# P03_Processor_1_of_3_JTAG_Header.net
KiCad netlist of a schematic drawn in Altium Designer
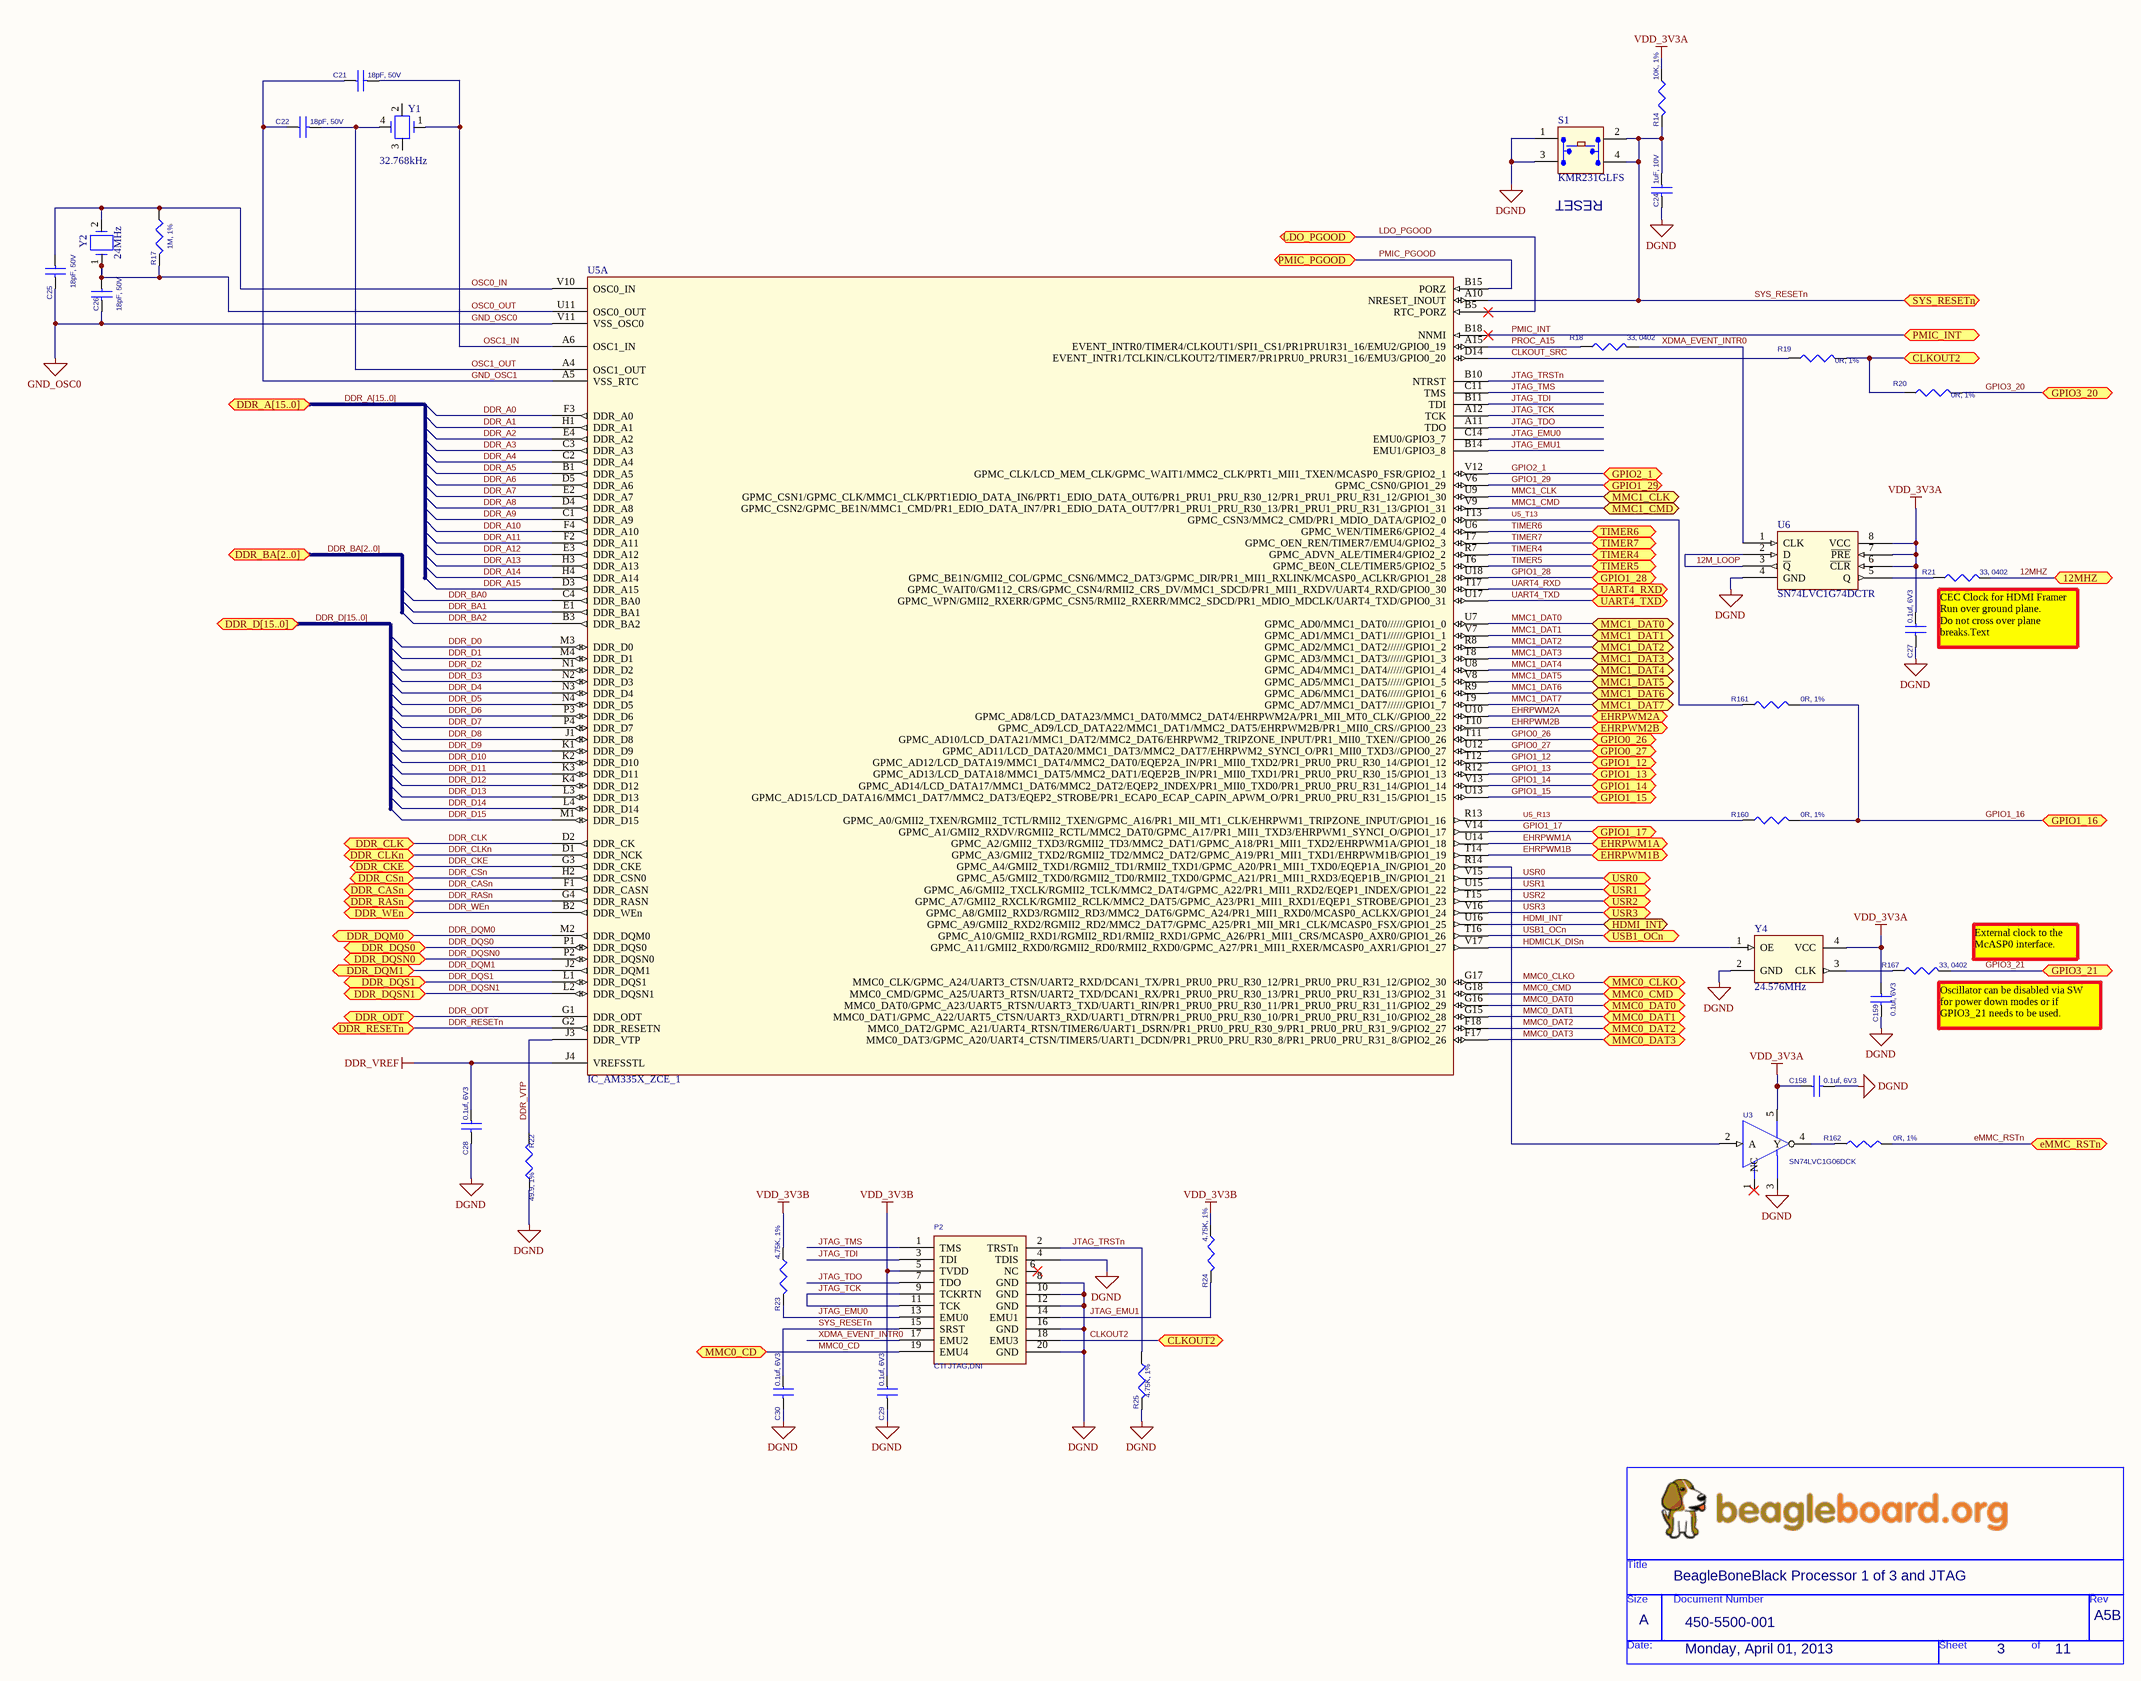
[diagram p0: P03_Processor 1 of 3, JTAG Header.SchDoc]

(export (version "E")
  (design (tool "Eeschema 10.0.6"))
  (components
    (comp (ref "C21")
      (value "18pF, 50V")
      (footprint "402")
      (description "CAP CER 18PF 50V 5% NP0 0402")
      (fields
        (field (name "MANUFACTURER") "TDK Corporation")
        (field (name "MANUFACTURER PART NUMBER") "C1005C0G1H180J050BA")
      )
      (libsource (lib "BEAGLEBONEBLACK_REV A5B") (part "CAP_18PF_COG_50V_5%_0402"))
    )
    (comp (ref "C22")
      (value "18pF, 50V")
      (footprint "402")
      (description "CAP CER 18PF 50V 5% NP0 0402")
      (fields
        (field (name "MANUFACTURER") "TDK Corporation")
        (field (name "MANUFACTURER PART NUMBER") "C1005C0G1H180J050BA")
      )
      (libsource (lib "BEAGLEBONEBLACK_REV A5B") (part "CAP_18PF_COG_50V_5%_0402"))
    )
    (comp (ref "C24")
      (value "1uF, 10V")
      (footprint "402")
      (description "CAP CER 1UF 10V 10% X5R 0402")
      (fields
        (field (name "MANUFACTURER") "AVX Corporation")
        (field (name "MANUFACTURER PART NUMBER") "0402ZD105KAT2A")
      )
      (libsource (lib "BEAGLEBONEBLACK_REV A5B") (part "CAP_1.0UF_X5R_10V_10%_0402"))
    )
    (comp (ref "C25")
      (value "18pF, 50V")
      (footprint "402")
      (description "CAP CER 18PF 50V 5% NP0 0402")
      (fields
        (field (name "MANUFACTURER") "TDK Corporation")
        (field (name "MANUFACTURER PART NUMBER") "C1005C0G1H180J050BA")
      )
      (libsource (lib "BEAGLEBONEBLACK_REV A5B") (part "CAP_18PF_COG_50V_5%_0402"))
    )
    (comp (ref "C26")
      (value "18pF, 50V")
      (footprint "402")
      (description "CAP CER 18PF 50V 5% NP0 0402")
      (fields
        (field (name "MANUFACTURER") "TDK Corporation")
        (field (name "MANUFACTURER PART NUMBER") "C1005C0G1H180J050BA")
      )
      (libsource (lib "BEAGLEBONEBLACK_REV A5B") (part "CAP_18PF_COG_50V_5%_0402"))
    )
    (comp (ref "C27")
      (value "0.1uf, 6V3")
      (footprint "402")
      (description "CAP CER 0.1UF 6.3V 10% X5R 0402")
      (fields
        (field (name "MANUFACTURER") "TDK Corporation")
        (field (name "MANUFACTURER PART NUMBER") "C1005X5R0J104K050BA")
      )
      (libsource (lib "BEAGLEBONEBLACK_REV A5B") (part "CAP_0.1uF_X7R_16V_10% 0402"))
    )
    (comp (ref "C28")
      (value "0.1uf, 6V3")
      (footprint "402")
      (description "CAP CER 0.1UF 6.3V 10% X5R 0402")
      (fields
        (field (name "MANUFACTURER") "TDK Corporation")
        (field (name "MANUFACTURER PART NUMBER") "C1005X5R0J104K050BA")
      )
      (libsource (lib "BEAGLEBONEBLACK_REV A5B") (part "CAP_0.1uF_X7R_16V_10% 0402"))
    )
    (comp (ref "C29")
      (value "0.1uf, 6V3")
      (footprint "402")
      (description "CAP CER 0.1UF 6.3V 10% X5R 0402")
      (fields
        (field (name "MANUFACTURER") "TDK Corporation")
        (field (name "MANUFACTURER PART NUMBER") "C1005X5R0J104K050BA")
      )
      (libsource (lib "BEAGLEBONEBLACK_REV A5B") (part "CAP_0.1uF_X7R_16V_10% 0402"))
    )
    (comp (ref "C30")
      (value "0.1uf, 6V3")
      (footprint "402")
      (description "CAP CER 0.1UF 6.3V 10% X5R 0402")
      (fields
        (field (name "MANUFACTURER") "TDK Corporation")
        (field (name "MANUFACTURER PART NUMBER") "C1005X5R0J104K050BA")
      )
      (libsource (lib "BEAGLEBONEBLACK_REV A5B") (part "CAP_0.1uF_X7R_16V_10% 0402"))
    )
    (comp (ref "C158")
      (value "0.1uf, 6V3")
      (footprint "402")
      (description "CAP CER 0.1UF 6.3V 10% X5R 0402")
      (fields
        (field (name "MANUFACTURER") "TDK Corporation")
        (field (name "MANUFACTURER PART NUMBER") "C1005X5R0J104K050BA")
      )
      (libsource (lib "BEAGLEBONEBLACK_REV A5B") (part "CAP_0.1uF_X7R_16V_10% 0402"))
    )
    (comp (ref "C159")
      (value "0.1uf, 6V3")
      (footprint "402")
      (description "CAP CER 0.1UF 6.3V 10% X5R 0402")
      (fields
        (field (name "MANUFACTURER") "TDK Corporation")
        (field (name "MANUFACTURER PART NUMBER") "C1005X5R0J104K050BA")
      )
      (libsource (lib "BEAGLEBONEBLACK_REV A5B") (part "CAP_0.1uF_X7R_16V_10% 0402"))
    )
    (comp (ref "P2")
      (value "CTI JTAG,DNI")
      (description "Dual Line Header 10x2pin Tin")
      (fields
        (field (name "MANUFACTURER") "Samtec Inc")
        (field (name "MANUFACTURER PART NUMBER") "FTR-110-03-G-D-06")
      )
      (libsource (lib "BEAGLEBONEBLACK_REV A5B") (part "HDR_10x2_CJTAG"))
    )
    (comp (ref "R14")
      (value "10K, 1%")
      (footprint "402")
      (description "RES 10K OHM 1/16W 5% 0402 SMD")
      (fields
        (field (name "MANUFACTURER") "Rohm Semiconductor")
        (field (name "MANUFACTURER PART NUMBER") "MCR01MZPJ103")
      )
      (libsource (lib "BEAGLEBONEBLACK_REV A5B") (part "RES_10K_1/16W_1%_0402"))
    )
    (comp (ref "R17")
      (value "1M, 1%")
      (footprint "402")
      (description "Resistor 1Mohm 1/16W 1% 0402")
      (fields
        (field (name "MANUFACTURER") "Stackpole Electronics Inc")
        (field (name "MANUFACTURER PART NUMBER") "RMCF0402FT1M00")
      )
      (libsource (lib "BEAGLEBONEBLACK_REV A5B") (part "RES_1M_1/16W_1%_0402"))
    )
    (comp (ref "R18")
      (value "33, 0402")
      (footprint "402")
      (description "RES 33 OHM 1/16W 5% 0402 SMD")
      (fields
        (field (name "MANUFACTURER") "Panasonic Electronic Components")
        (field (name "MANUFACTURER PART NUMBER") "ERJ-2GEJ330X")
      )
      (libsource (lib "BEAGLEBONEBLACK_REV A5B") (part "RES_33_0402"))
    )
    (comp (ref "R19")
      (value "0R, 1%")
      (footprint "402")
      (description "RES 0.0 OHM 1/16W 0402 SMD")
      (fields
        (field (name "MANUFACTURER") "Yageo")
        (field (name "MANUFACTURER PART NUMBER") "RC0402JR-070RL")
      )
      (libsource (lib "BEAGLEBONEBLACK_REV A5B") (part "RES_0_1/16W_1%_0402"))
    )
    (comp (ref "R20")
      (value "0R, 1%")
      (footprint "402")
      (description "RES 0.0 OHM 1/16W 0402 SMD")
      (fields
        (field (name "MANUFACTURER") "Yageo")
        (field (name "MANUFACTURER PART NUMBER") "RC0402JR-070RL")
      )
      (libsource (lib "BEAGLEBONEBLACK_REV A5B") (part "RES_0_1/16W_1%_0402"))
    )
    (comp (ref "R21")
      (value "33, 0402")
      (footprint "402")
      (description "RES 33 OHM 1/16W 5% 0402 SMD")
      (fields
        (field (name "MANUFACTURER") "Panasonic Electronic Components")
        (field (name "MANUFACTURER PART NUMBER") "ERJ-2GEJ330X")
      )
      (libsource (lib "BEAGLEBONEBLACK_REV A5B") (part "RES_33_0402"))
    )
    (comp (ref "R22")
      (value "49.9, 1%")
      (footprint "402")
      (description "RES 49.9 OHM 1/16W 1% 0402 SMD")
      (fields
        (field (name "MANUFACTURER") "Yageo")
        (field (name "MANUFACTURER PART NUMBER") "RC0402FR-0749R9L")
      )
      (libsource (lib "BEAGLEBONEBLACK_REV A5B") (part "RES_4.7K_0402"))
    )
    (comp (ref "R23")
      (value "4.75K, 1%")
      (footprint "402")
      (description "RES 4.75K 1/16W 1% 0402 SMD")
      (fields
        (field (name "MANUFACTURER") "Stackpole Electronics Inc")
        (field (name "MANUFACTURER PART NUMBER") "RMCF0402FT4K75")
      )
      (libsource (lib "BEAGLEBONEBLACK_REV A5B") (part "RES_4.7K_0402"))
    )
    (comp (ref "R24")
      (value "4.75K, 1%")
      (footprint "402")
      (description "RES 4.75K 1/16W 1% 0402 SMD")
      (fields
        (field (name "MANUFACTURER") "Stackpole Electronics Inc")
        (field (name "MANUFACTURER PART NUMBER") "RMCF0402FT4K75")
      )
      (libsource (lib "BEAGLEBONEBLACK_REV A5B") (part "RES_4.7K_0402"))
    )
    (comp (ref "R25")
      (value "4.75K, 1%")
      (footprint "402")
      (description "RES 4.75K 1/16W 1% 0402 SMD")
      (fields
        (field (name "MANUFACTURER") "Stackpole Electronics Inc")
        (field (name "MANUFACTURER PART NUMBER") "RMCF0402FT4K75")
      )
      (libsource (lib "BEAGLEBONEBLACK_REV A5B") (part "RES_4.7K_0402"))
    )
    (comp (ref "R160")
      (value "0R, 1%")
      (footprint "402")
      (description "RES 0.0 OHM 1/16W 0402 SMD")
      (fields
        (field (name "MANUFACTURER") "Yageo")
        (field (name "MANUFACTURER PART NUMBER") "RC0402JR-070RL")
      )
      (libsource (lib "BEAGLEBONEBLACK_REV A5B") (part "RES_0_1/16W_1%_0402"))
    )
    (comp (ref "R161")
      (value "0R, 1%")
      (footprint "402")
      (description "RES 0.0 OHM 1/16W 0402 SMD")
      (fields
        (field (name "MANUFACTURER") "Yageo")
        (field (name "MANUFACTURER PART NUMBER") "RC0402JR-070RL")
      )
      (libsource (lib "BEAGLEBONEBLACK_REV A5B") (part "RES_0_1/16W_1%_0402"))
    )
    (comp (ref "R162")
      (value "0R, 1%")
      (footprint "402")
      (description "RES 0.0 OHM 1/16W 0402 SMD")
      (fields
        (field (name "MANUFACTURER") "Yageo")
        (field (name "MANUFACTURER PART NUMBER") "RC0402JR-070RL")
      )
      (libsource (lib "BEAGLEBONEBLACK_REV A5B") (part "RES_0_1/16W_1%_0402"))
    )
    (comp (ref "R167")
      (value "33, 0402")
      (footprint "402")
      (description "RES 33 OHM 1/16W 5% 0402 SMD")
      (fields
        (field (name "MANUFACTURER") "Panasonic Electronic Components")
        (field (name "MANUFACTURER PART NUMBER") "ERJ-2GEJ330X")
      )
      (libsource (lib "BEAGLEBONEBLACK_REV A5B") (part "RES_33_0402"))
    )
    (comp (ref "S1")
      (value "KMR231GLFS")
      (footprint "SW4SMD_63X161LS")
      (description "Microminiature Tact Switch for SMT")
      (fields (field (name "MANUFACTURER") "C&K Components"))
      (libsource (lib "BEAGLEBONEBLACK_REV A5B") (part "KMR2"))
    )
    (comp (ref "U3")
      (value "SN74LVC1G06DCK")
      (footprint "DCK5_2P15X1P4")
      (description "IC INVERTER SINGLE 1INPUT SC705")
      (fields
        (field (name "MANUFACTURER") "Texas Instruments")
        (field (name "MANUFACTURER PART NUMBER") "SN74LVC1G06DCKTG4")
      )
      (libsource (lib "BEAGLEBONEBLACK_REV A5B") (part "SN74LVC1G06DCK"))
    )
    (comp (ref "U5")
      (value "IC_AM335X_ZCE_1")
      (footprint "am33xx_15x15")
      (description "SubArctic Cortex A8 Processor 15x15")
      (fields
        (field (name "MANUFACTURER") "Texas Instruments")
        (field (name "MANUFACTURER PART NUMBER") "XAM3359ZCZ")
      )
      (libsource (lib "BEAGLEBONEBLACK_REV A5B") (part "IC_AM335X_ZCE_1"))
    )
    (comp (ref "U6")
      (value "SN74LVC1G74DCTR")
      (footprint "SOP8_DCT")
      (description "SINGLE  POSITIVE-EDGE-TRIGGERED  D-TYPE  FLIP-FLOP WITH  CLEAR  AND  PRESET")
      (fields (field (name "MANUFACTURER") "Texas Instruments"))
      (libsource (lib "BEAGLEBONEBLACK_REV A5B") (part "SN74LVC1G74DCTR"))
    )
    (comp (ref "Y1")
      (value "32.768kHz")
      (footprint "XTAL4_126-216SMD")
      (description "CRYSTAL 32.768KHZ 12.5PF SMD")
      (fields
        (field (name "MANUFACTURER") "Citizen Finetech Miyota")
        (field (name "MANUFACTURER PART NUMBER") "CM200C-32.768KAZF-UT")
      )
      (libsource (lib "BEAGLEBONEBLACK_REV A5B") (part "CRYS_32_768KHz_SMD32"))
    )
    (comp (ref "Y2")
      (value "24MHz")
      (footprint "XTAL150SMD_125X196")
      (description "CRYSTAL 24.000MHZ 18PF SMD")
      (fields
        (field (name "MANUFACTURER") "TXC CORPORATION")
        (field (name "MANUFACTURER PART NUMBER") "7A-24.000MAAJ-T")
      )
      (libsource (lib "BEAGLEBONEBLACK_REV A5B") (part "CRYS_24MHz_SCC"))
    )
    (comp (ref "Y4")
      (value "24.576MHz")
      (footprint "OSC4_61X65LS_79X98SMD")
      (fields
        (field (name "MANUFACTURER") "Abracon Corporation")
        (field (name "MANUFACTURER PART NUMBER") "ASDMB-24.576MHZ-LC-T")
      )
      (libsource (lib "BEAGLEBONEBLACK_REV A5B") (part "ASDMB"))
    )
  )
  (nets
    (net (code "1") (name "/12MHZ") (class "Default")
      (node (ref "R21") (pin "2") (pinfunction "2_2") (pintype "passive"))
    )
    (net (code "2") (name "/12M_LOOP") (class "Default")
      (node (ref "U6") (pin "2") (pinfunction "D_2") (pintype "input"))
      (node (ref "U6") (pin "3") (pinfunction "~{Q}_3") (pintype "output"))
    )
    (net (code "3") (name "/CLKOUT2") (class "Default")
      (node (ref "P2") (pin "18") (pinfunction "EMU3_18") (pintype "passive"))
      (node (ref "R19") (pin "2") (pinfunction "2_2") (pintype "passive"))
      (node (ref "R20") (pin "1") (pinfunction "1_1") (pintype "passive"))
    )
    (net (code "4") (name "/CLKOUT_SRC") (class "Default")
      (node (ref "R19") (pin "1") (pinfunction "1_1") (pintype "passive"))
      (node (ref "U5") (pin "D14") (pinfunction "EVENT_INTR1/TCLKIN/CLKOUT2/TIMER7/PR1PRU0_PRUR31_16/EMU3/GPIO0_20_D14") (pintype "bidirectional"))
    )
    (net (code "5") (name "/DDR_A0") (class "Default")
      (node (ref "U5") (pin "F3") (pinfunction "DDR_A0_F3") (pintype "output"))
    )
    (net (code "6") (name "/DDR_A1") (class "Default")
      (node (ref "U5") (pin "H1") (pinfunction "DDR_A1_H1") (pintype "output"))
    )
    (net (code "7") (name "/DDR_A2") (class "Default")
      (node (ref "U5") (pin "E4") (pinfunction "DDR_A2_E4") (pintype "output"))
    )
    (net (code "8") (name "/DDR_A3") (class "Default")
      (node (ref "U5") (pin "C3") (pinfunction "DDR_A3_C3") (pintype "output"))
    )
    (net (code "9") (name "/DDR_A4") (class "Default")
      (node (ref "U5") (pin "C2") (pinfunction "DDR_A4_C2") (pintype "output"))
    )
    (net (code "10") (name "/DDR_A5") (class "Default")
      (node (ref "U5") (pin "B1") (pinfunction "DDR_A5_B1") (pintype "output"))
    )
    (net (code "11") (name "/DDR_A6") (class "Default")
      (node (ref "U5") (pin "D5") (pinfunction "DDR_A6_D5") (pintype "output"))
    )
    (net (code "12") (name "/DDR_A7") (class "Default")
      (node (ref "U5") (pin "E2") (pinfunction "DDR_A7_E2") (pintype "output"))
    )
    (net (code "13") (name "/DDR_A8") (class "Default")
      (node (ref "U5") (pin "D4") (pinfunction "DDR_A8_D4") (pintype "output"))
    )
    (net (code "14") (name "/DDR_A9") (class "Default")
      (node (ref "U5") (pin "C1") (pinfunction "DDR_A9_C1") (pintype "output"))
    )
    (net (code "15") (name "/DDR_A10") (class "Default")
      (node (ref "U5") (pin "F4") (pinfunction "DDR_A10_F4") (pintype "output"))
    )
    (net (code "16") (name "/DDR_A11") (class "Default")
      (node (ref "U5") (pin "F2") (pinfunction "DDR_A11_F2") (pintype "output"))
    )
    (net (code "17") (name "/DDR_A12") (class "Default")
      (node (ref "U5") (pin "E3") (pinfunction "DDR_A12_E3") (pintype "output"))
    )
    (net (code "18") (name "/DDR_A13") (class "Default")
      (node (ref "U5") (pin "H3") (pinfunction "DDR_A13_H3") (pintype "output"))
    )
    (net (code "19") (name "/DDR_A14") (class "Default")
      (node (ref "U5") (pin "H4") (pinfunction "DDR_A14_H4") (pintype "output"))
    )
    (net (code "20") (name "/DDR_A15") (class "Default")
      (node (ref "U5") (pin "D3") (pinfunction "DDR_A15_D3") (pintype "output"))
    )
    (net (code "22") (name "/DDR_BA0") (class "Default")
      (node (ref "U5") (pin "C4") (pinfunction "DDR_BA0_C4") (pintype "output"))
    )
    (net (code "23") (name "/DDR_BA1") (class "Default")
      (node (ref "U5") (pin "E1") (pinfunction "DDR_BA1_E1") (pintype "output"))
    )
    (net (code "24") (name "/DDR_BA2") (class "Default")
      (node (ref "U5") (pin "B3") (pinfunction "DDR_BA2_B3") (pintype "output"))
    )
    (net (code "26") (name "/DDR_CASn") (class "Default")
      (node (ref "U5") (pin "F1") (pinfunction "DDR_CASN_F1") (pintype "output"))
    )
    (net (code "27") (name "/DDR_CKE") (class "Default")
      (node (ref "U5") (pin "G3") (pinfunction "DDR_CKE_G3") (pintype "output"))
    )
    (net (code "28") (name "/DDR_CLK") (class "Default")
      (node (ref "U5") (pin "D2") (pinfunction "DDR_CK_D2") (pintype "output"))
    )
    (net (code "29") (name "/DDR_CLKn") (class "Default")
      (node (ref "U5") (pin "D1") (pinfunction "DDR_NCK_D1") (pintype "output"))
    )
    (net (code "30") (name "/DDR_CSn") (class "Default")
      (node (ref "U5") (pin "H2") (pinfunction "DDR_CSN0_H2") (pintype "output"))
    )
    (net (code "31") (name "/DDR_D0") (class "Default")
      (node (ref "U5") (pin "M3") (pinfunction "DDR_D0_M3") (pintype "bidirectional"))
    )
    (net (code "32") (name "/DDR_D1") (class "Default")
      (node (ref "U5") (pin "M4") (pinfunction "DDR_D1_M4") (pintype "bidirectional"))
    )
    (net (code "33") (name "/DDR_D2") (class "Default")
      (node (ref "U5") (pin "N1") (pinfunction "DDR_D2_N1") (pintype "bidirectional"))
    )
    (net (code "34") (name "/DDR_D3") (class "Default")
      (node (ref "U5") (pin "N2") (pinfunction "DDR_D3_N2") (pintype "bidirectional"))
    )
    (net (code "35") (name "/DDR_D4") (class "Default")
      (node (ref "U5") (pin "N3") (pinfunction "DDR_D4_N3") (pintype "bidirectional"))
    )
    (net (code "36") (name "/DDR_D5") (class "Default")
      (node (ref "U5") (pin "N4") (pinfunction "DDR_D5_N4") (pintype "bidirectional"))
    )
    (net (code "37") (name "/DDR_D6") (class "Default")
      (node (ref "U5") (pin "P3") (pinfunction "DDR_D6_P3") (pintype "bidirectional"))
    )
    (net (code "38") (name "/DDR_D7") (class "Default")
      (node (ref "U5") (pin "P4") (pinfunction "DDR_D7_P4") (pintype "bidirectional"))
    )
    (net (code "39") (name "/DDR_D8") (class "Default")
      (node (ref "U5") (pin "J1") (pinfunction "DDR_D8_J1") (pintype "bidirectional"))
    )
    (net (code "40") (name "/DDR_D9") (class "Default")
      (node (ref "U5") (pin "K1") (pinfunction "DDR_D9_K1") (pintype "bidirectional"))
    )
    (net (code "41") (name "/DDR_D10") (class "Default")
      (node (ref "U5") (pin "K2") (pinfunction "DDR_D10_K2") (pintype "bidirectional"))
    )
    (net (code "42") (name "/DDR_D11") (class "Default")
      (node (ref "U5") (pin "K3") (pinfunction "DDR_D11_K3") (pintype "bidirectional"))
    )
    (net (code "43") (name "/DDR_D12") (class "Default")
      (node (ref "U5") (pin "K4") (pinfunction "DDR_D12_K4") (pintype "bidirectional"))
    )
    (net (code "44") (name "/DDR_D13") (class "Default")
      (node (ref "U5") (pin "L3") (pinfunction "DDR_D13_L3") (pintype "bidirectional"))
    )
    (net (code "45") (name "/DDR_D14") (class "Default")
      (node (ref "U5") (pin "L4") (pinfunction "DDR_D14_L4") (pintype "bidirectional"))
    )
    (net (code "46") (name "/DDR_D15") (class "Default")
      (node (ref "U5") (pin "M1") (pinfunction "DDR_D15_M1") (pintype "bidirectional"))
    )
    (net (code "47") (name "/DDR_DQM0") (class "Default")
      (node (ref "U5") (pin "M2") (pinfunction "DDR_DQM0_M2") (pintype "output"))
    )
    (net (code "48") (name "/DDR_DQM1") (class "Default")
      (node (ref "U5") (pin "J2") (pinfunction "DDR_DQM1_J2") (pintype "output"))
    )
    (net (code "49") (name "/DDR_DQS0") (class "Default")
      (node (ref "U5") (pin "P1") (pinfunction "DDR_DQS0_P1") (pintype "bidirectional"))
    )
    (net (code "50") (name "/DDR_DQS1") (class "Default")
      (node (ref "U5") (pin "L1") (pinfunction "DDR_DQS1_L1") (pintype "bidirectional"))
    )
    (net (code "51") (name "/DDR_DQSN0") (class "Default")
      (node (ref "U5") (pin "P2") (pinfunction "DDR_DQSN0_P2") (pintype "bidirectional"))
    )
    (net (code "52") (name "/DDR_DQSN1") (class "Default")
      (node (ref "U5") (pin "L2") (pinfunction "DDR_DQSN1_L2") (pintype "bidirectional"))
    )
    (net (code "54") (name "/DDR_ODT") (class "Default")
      (node (ref "U5") (pin "G1") (pinfunction "DDR_ODT_G1") (pintype "passive"))
    )
    (net (code "55") (name "/DDR_RASn") (class "Default")
      (node (ref "U5") (pin "G4") (pinfunction "DDR_RASN_G4") (pintype "output"))
    )
    (net (code "56") (name "/DDR_RESETn") (class "Default")
      (node (ref "U5") (pin "G2") (pinfunction "DDR_RESETN_G2") (pintype "output"))
    )
    (net (code "57") (name "/DDR_VTP") (class "Default")
      (node (ref "R22") (pin "2") (pinfunction "2_2") (pintype "passive"))
      (node (ref "U5") (pin "J3") (pinfunction "DDR_VTP_J3") (pintype "passive"))
    )
    (net (code "58") (name "/DDR_WEn") (class "Default")
      (node (ref "U5") (pin "B2") (pinfunction "DDR_WEn_B2") (pintype "output"))
    )
    (net (code "59") (name "/EHRPWM1A") (class "Default")
      (node (ref "U5") (pin "U14") (pinfunction "GPMC_A2/GMII2_TXD3/RGMII2_TD3/MMC2_DAT1/GPMC_A18/PR1_MII1_TXD2/EHRPWM1A/GPIO1_18_U14") (pintype "output"))
    )
    (net (code "60") (name "/EHRPWM1B") (class "Default")
      (node (ref "U5") (pin "T14") (pinfunction "GPMC_A3/GMII2_TXD2/RGMII2_TD2/MMC2_DAT2/GPMC_A19/PR1_MII1_TXD1/EHRPWM1B/GPIO1_19_T14") (pintype "output"))
    )
    (net (code "61") (name "/EHRPWM2A") (class "Default")
      (node (ref "U5") (pin "U10") (pinfunction "GPMC_AD8/LCD_DATA23/MMC1_DAT0/MMC2_DAT4/EHRPWM2A/PR1_MII_MT0_CLK//GPIO0_22_U10") (pintype "bidirectional"))
    )
    (net (code "62") (name "/EHRPWM2B") (class "Default")
      (node (ref "U5") (pin "T10") (pinfunction "GPMC_AD9/LCD_DATA22/MMC1_DAT1/MMC2_DAT5/EHRPWM2B/PR1_MII0_CRS//GPIO0_23_T10") (pintype "bidirectional"))
    )
    (net (code "63") (name "/GND_OSC1") (class "Default")
      (node (ref "C21") (pin "1") (pinfunction "1_1") (pintype "passive"))
      (node (ref "C22") (pin "1") (pinfunction "1_1") (pintype "passive"))
      (node (ref "U5") (pin "A5") (pinfunction "VSS_RTC_A5") (pintype "power_in"))
    )
    (net (code "64") (name "/GPIO0_26") (class "Default")
      (node (ref "U5") (pin "T11") (pinfunction "GPMC_AD10/LCD_DATA21/MMC1_DAT2/MMC2_DAT6/EHRPWM2_TRIPZONE_INPUT/PR1_MII0_TXEN//GPIO0_26_T11") (pintype "bidirectional"))
    )
    (net (code "65") (name "/GPIO0_27") (class "Default")
      (node (ref "U5") (pin "U12") (pinfunction "GPMC_AD11/LCD_DATA20/MMC1_DAT3/MMC2_DAT7/EHRPWM2_SYNCI_O/PR1_MII0_TXD3//GPIO0_27_U12") (pintype "bidirectional"))
    )
    (net (code "66") (name "/GPIO1_12") (class "Default")
      (node (ref "U5") (pin "T12") (pinfunction "GPMC_AD12/LCD_DATA19/MMC1_DAT4/MMC2_DAT0/EQEP2A_IN/PR1_MII0_TXD2/PR1_PRU0_PRU_R30_14/GPIO1_12_T12") (pintype "bidirectional"))
    )
    (net (code "67") (name "/GPIO1_13") (class "Default")
      (node (ref "U5") (pin "R12") (pinfunction "GPMC_AD13/LCD_DATA18/MMC1_DAT5/MMC2_DAT1/EQEP2B_IN/PR1_MII0_TXD1/PR1_PRU0_PRU_R30_15/GPIO1_13_R12") (pintype "bidirectional"))
    )
    (net (code "68") (name "/GPIO1_14") (class "Default")
      (node (ref "U5") (pin "V13") (pinfunction "GPMC_AD14/LCD_DATA17/MMC1_DAT6/MMC2_DAT2/EQEP2_INDEX/PR1_MII0_TXD0/PR1_PRU0_PRU_R31_14/GPIO1_14_V13") (pintype "bidirectional"))
    )
    (net (code "69") (name "/GPIO1_15") (class "Default")
      (node (ref "U5") (pin "U13") (pinfunction "GPMC_AD15/LCD_DATA16/MMC1_DAT7/MMC2_DAT3/EQEP2_STROBE/PR1_ECAP0_ECAP_CAPIN_APWM_O/PR1_PRU0_PRU_R31_15/GPIO1_15_U13") (pintype "bidirectional"))
    )
    (net (code "70") (name "/GPIO1_16") (class "Default")
      (node (ref "R160") (pin "2") (pinfunction "2_2") (pintype "passive"))
      (node (ref "R161") (pin "2") (pinfunction "2_2") (pintype "passive"))
    )
    (net (code "71") (name "/GPIO1_17") (class "Default")
      (node (ref "U5") (pin "V14") (pinfunction "GPMC_A1/GMII2_RXDV/RGMII2_RCTL/MMC2_DAT0/GPMC_A17/PR1_MII1_TXD3/EHRPWM1_SYNCI_O/GPIO1_17_V14") (pintype "output"))
    )
    (net (code "72") (name "/GPIO1_28") (class "Default")
      (node (ref "U5") (pin "U18") (pinfunction "GPMC_BE1N/GMII2_COL/GPMC_CSN6/MMC2_DAT3/GPMC_DIR/PR1_MII1_RXLINK/MCASP0_ACLKR/GPIO1_28_U18") (pintype "bidirectional"))
    )
    (net (code "73") (name "/GPIO1_29") (class "Default")
      (node (ref "U5") (pin "V6") (pinfunction "GPMC_CSN0/GPIO1_29_V6") (pintype "bidirectional"))
    )
    (net (code "74") (name "/GPIO2_1") (class "Default")
      (node (ref "U5") (pin "V12") (pinfunction "GPMC_CLK/LCD_MEM_CLK/GPMC_WAIT1/MMC2_CLK/PRT1_MII1_TXEN/MCASP0_FSR/GPIO2_1_V12") (pintype "bidirectional"))
    )
    (net (code "75") (name "/GPIO3_20") (class "Default")
      (node (ref "R20") (pin "2") (pinfunction "2_2") (pintype "passive"))
    )
    (net (code "76") (name "/GPIO3_21") (class "Default")
      (node (ref "R167") (pin "2") (pinfunction "2_2") (pintype "passive"))
    )
    (net (code "77") (name "/HDMICLK_DISn") (class "Default")
      (node (ref "U5") (pin "V17") (pinfunction "GPMC_A11/GMII2_RXD0/RGMII2_RD0/RMII2_RXD0/GPMC_A27/PR1_MII1_RXER/MCASP0_AXR1/GPIO1_27_V17") (pintype "output"))
      (node (ref "Y4") (pin "1") (pinfunction "OE_1") (pintype "input"))
    )
    (net (code "78") (name "/HDMI_INT") (class "Default")
      (node (ref "U5") (pin "U16") (pinfunction "GPMC_A9/GMII2_RXD2/RGMII2_RD2/MMC2_DAT7/GPMC_A25/PR1_MII_MR1_CLK/MCASP0_FSX/GPIO1_25_U16") (pintype "output"))
    )
    (net (code "79") (name "/JTAG_EMU0") (class "Default")
      (node (ref "P2") (pin "13") (pinfunction "EMU0_13") (pintype "passive"))
      (node (ref "R23") (pin "2") (pinfunction "2_2") (pintype "passive"))
      (node (ref "U5") (pin "C14") (pinfunction "EMU0/GPIO3_7_C14") (pintype "passive"))
    )
    (net (code "80") (name "/JTAG_EMU1") (class "Default")
      (node (ref "P2") (pin "14") (pinfunction "EMU1_14") (pintype "passive"))
      (node (ref "R24") (pin "2") (pinfunction "2_2") (pintype "passive"))
      (node (ref "U5") (pin "B14") (pinfunction "EMU1/GPIO3_8_B14") (pintype "passive"))
    )
    (net (code "81") (name "/JTAG_TCK") (class "Default")
      (node (ref "P2") (pin "11") (pinfunction "TCK_11") (pintype "passive"))
      (node (ref "P2") (pin "9") (pinfunction "TCKRTN_9") (pintype "passive"))
      (node (ref "U5") (pin "A12") (pinfunction "TCK_A12") (pintype "passive"))
    )
    (net (code "82") (name "/JTAG_TDI") (class "Default")
      (node (ref "P2") (pin "3") (pinfunction "TDI_3") (pintype "passive"))
      (node (ref "U5") (pin "B11") (pinfunction "TDI_B11") (pintype "passive"))
    )
    (net (code "83") (name "/JTAG_TDO") (class "Default")
      (node (ref "P2") (pin "7") (pinfunction "TDO_7") (pintype "passive"))
      (node (ref "U5") (pin "A11") (pinfunction "TDO_A11") (pintype "passive"))
    )
    (net (code "84") (name "/JTAG_TMS") (class "Default")
      (node (ref "P2") (pin "1") (pinfunction "TMS_1") (pintype "passive"))
      (node (ref "U5") (pin "C11") (pinfunction "TMS_C11") (pintype "passive"))
    )
    (net (code "85") (name "/JTAG_TRSTn") (class "Default")
      (node (ref "P2") (pin "2") (pinfunction "TRSTn_2") (pintype "passive"))
      (node (ref "R25") (pin "1") (pinfunction "1_1") (pintype "passive"))
      (node (ref "U5") (pin "B10") (pinfunction "NTRST_B10") (pintype "passive"))
    )
    (net (code "86") (name "/LDO_PGOOD") (class "Default")
      (node (ref "U5") (pin "B5") (pinfunction "RTC_PORZ_B5") (pintype "input+no_connect"))
    )
    (net (code "87") (name "/MMC0_CD") (class "Default")
      (node (ref "P2") (pin "19") (pinfunction "EMU4_19") (pintype "passive"))
    )
    (net (code "88") (name "/MMC0_CLKO") (class "Default")
      (node (ref "U5") (pin "G17") (pinfunction "MMC0_CLK/GPMC_A24/UART3_CTSN/UART2_RXD/DCAN1_TX/PR1_PRU0_PRU_R30_12/PR1_PRU0_PRU_R31_12/GPIO2_30_G17") (pintype "bidirectional"))
    )
    (net (code "89") (name "/MMC0_CMD") (class "Default")
      (node (ref "U5") (pin "G18") (pinfunction "MMC0_CMD/GPMC_A25/UART3_RTSN/UART2_TXD/DCAN1_RX/PR1_PRU0_PRU_R30_13/PR1_PRU0_PRU_R31_13/GPIO2_31_G18") (pintype "bidirectional"))
    )
    (net (code "90") (name "/MMC0_DAT0") (class "Default")
      (node (ref "U5") (pin "G16") (pinfunction "MMC0_DAT0/GPMC_A23/UART5_RTSN/UART3_TXD/UART1_RIN/PR1_PRU0_PRU_R30_11/PR1_PRU0_PRU_R31_11/GPIO2_29_G16") (pintype "bidirectional"))
    )
    (net (code "91") (name "/MMC0_DAT1") (class "Default")
      (node (ref "U5") (pin "G15") (pinfunction "MMC0_DAT1/GPMC_A22/UART5_CTSN/UART3_RXD/UART1_DTRN/PR1_PRU0_PRU_R30_10/PR1_PRU0_PRU_R31_10/GPIO2_28_G15") (pintype "bidirectional"))
    )
    (net (code "92") (name "/MMC0_DAT2") (class "Default")
      (node (ref "U5") (pin "F18") (pinfunction "MMC0_DAT2/GPMC_A21/UART4_RTSN/TIMER6/UART1_DSRN/PR1_PRU0_PRU_R30_9/PR1_PRU0_PRU_R31_9/GPIO2_27_F18") (pintype "bidirectional"))
    )
    (net (code "93") (name "/MMC0_DAT3") (class "Default")
      (node (ref "U5") (pin "F17") (pinfunction "MMC0_DAT3/GPMC_A20/UART4_CTSN/TIMER5/UART1_DCDN/PR1_PRU0_PRU_R30_8/PR1_PRU0_PRU_R31_8/GPIO2_26_F17") (pintype "bidirectional"))
    )
    (net (code "94") (name "/MMC1_CLK") (class "Default")
      (node (ref "U5") (pin "U9") (pinfunction "GPMC_CSN1/GPMC_CLK/MMC1_CLK/PRT1EDIO_DATA_IN6/PRT1_EDIO_DATA_OUT6/PR1_PRU1_PRU_R30_12/PR1_PRU1_PRU_R31_12/GPIO1_30_U9") (pintype "bidirectional"))
    )
    (net (code "95") (name "/MMC1_CMD") (class "Default")
      (node (ref "U5") (pin "V9") (pinfunction "GPMC_CSN2/GPMC_BE1N/MMC1_CMD/PR1_EDIO_DATA_IN7/PR1_EDIO_DATA_OUT7/PR1_PRU1_PRU_R30_13/PR1_PRU1_PRU_R31_13/GPIO1_31_V9") (pintype "bidirectional"))
    )
    (net (code "96") (name "/MMC1_DAT0") (class "Default")
      (node (ref "U5") (pin "U7") (pinfunction "GPMC_AD0/MMC1_DAT0//////GPIO1_0_U7") (pintype "bidirectional"))
    )
    (net (code "97") (name "/MMC1_DAT1") (class "Default")
      (node (ref "U5") (pin "V7") (pinfunction "GPMC_AD1/MMC1_DAT1//////GPIO1_1_V7") (pintype "bidirectional"))
    )
    (net (code "98") (name "/MMC1_DAT2") (class "Default")
      (node (ref "U5") (pin "R8") (pinfunction "GPMC_AD2/MMC1_DAT2//////GPIO1_2_R8") (pintype "bidirectional"))
    )
    (net (code "99") (name "/MMC1_DAT3") (class "Default")
      (node (ref "U5") (pin "T8") (pinfunction "GPMC_AD3/MMC1_DAT3//////GPIO1_3_T8") (pintype "bidirectional"))
    )
    (net (code "100") (name "/MMC1_DAT4") (class "Default")
      (node (ref "U5") (pin "U8") (pinfunction "GPMC_AD4/MMC1_DAT4//////GPIO1_4_U8") (pintype "bidirectional"))
    )
    (net (code "101") (name "/MMC1_DAT5") (class "Default")
      (node (ref "U5") (pin "V8") (pinfunction "GPMC_AD5/MMC1_DAT5//////GPIO1_5_V8") (pintype "bidirectional"))
    )
    (net (code "102") (name "/MMC1_DAT6") (class "Default")
      (node (ref "U5") (pin "R9") (pinfunction "GPMC_AD6/MMC1_DAT6//////GPIO1_6_R9") (pintype "bidirectional"))
    )
    (net (code "103") (name "/MMC1_DAT7") (class "Default")
      (node (ref "U5") (pin "T9") (pinfunction "GPMC_AD7/MMC1_DAT7//////GPIO1_7_T9") (pintype "bidirectional"))
    )
    (net (code "104") (name "/OSC0_IN") (class "Default")
      (node (ref "C25") (pin "1") (pinfunction "1_1") (pintype "passive"))
      (node (ref "R17") (pin "1") (pinfunction "1_1") (pintype "passive"))
      (node (ref "U5") (pin "V10") (pinfunction "OSC0_IN_V10") (pintype "passive"))
      (node (ref "Y2") (pin "2") (pinfunction "2_2") (pintype "passive"))
    )
    (net (code "105") (name "/OSC0_OUT") (class "Default")
      (node (ref "C26") (pin "1") (pinfunction "1_1") (pintype "passive"))
      (node (ref "R17") (pin "2") (pinfunction "2_2") (pintype "passive"))
      (node (ref "U5") (pin "U11") (pinfunction "OSC0_OUT_U11") (pintype "passive"))
      (node (ref "Y2") (pin "1") (pinfunction "1_1") (pintype "passive"))
    )
    (net (code "106") (name "/OSC1_IN") (class "Default")
      (node (ref "C21") (pin "2") (pinfunction "2_2") (pintype "passive"))
      (node (ref "U5") (pin "A6") (pinfunction "OSC1_IN_A6") (pintype "passive"))
      (node (ref "Y1") (pin "1") (pinfunction "1_1") (pintype "passive"))
    )
    (net (code "107") (name "/OSC1_OUT") (class "Default")
      (node (ref "C22") (pin "2") (pinfunction "2_2") (pintype "passive"))
      (node (ref "U5") (pin "A4") (pinfunction "OSC1_OUT_A4") (pintype "passive"))
      (node (ref "Y1") (pin "4") (pinfunction "4_4") (pintype "passive"))
    )
    (net (code "108") (name "/PMIC_INT") (class "Default")
      (node (ref "U5") (pin "B18") (pinfunction "NNMI_B18") (pintype "input+no_connect"))
    )
    (net (code "109") (name "/PMIC_PGOOD") (class "Default")
      (node (ref "U5") (pin "B15") (pinfunction "PORZ_B15") (pintype "input"))
    )
    (net (code "110") (name "/PROC_A15") (class "Default")
      (node (ref "R18") (pin "1") (pinfunction "1_1") (pintype "passive"))
      (node (ref "U5") (pin "A15") (pinfunction "EVENT_INTR0/TIMER4/CLKOUT1/SPI1_CS1/PR1PRU1R31_16/EMU2/GPIO0_19_A15") (pintype "bidirectional"))
    )
    (net (code "111") (name "/SYS_RESETn") (class "Default")
      (node (ref "C24") (pin "1") (pinfunction "1_1") (pintype "passive"))
      (node (ref "C30") (pin "1") (pinfunction "1_1") (pintype "passive"))
      (node (ref "P2") (pin "15") (pinfunction "SRST_15") (pintype "passive"))
      (node (ref "R14") (pin "2") (pinfunction "2_2") (pintype "passive"))
      (node (ref "S1") (pin "2") (pinfunction "A2_2") (pintype "passive"))
      (node (ref "S1") (pin "4") (pinfunction "4_4") (pintype "power_in"))
      (node (ref "U5") (pin "A10") (pinfunction "NRESET_INOUT_A10") (pintype "bidirectional"))
    )
    (net (code "112") (name "/TIMER4") (class "Default")
      (node (ref "U5") (pin "R7") (pinfunction "GPMC_ADVN_ALE/TIMER4/GPIO2_2_R7") (pintype "bidirectional"))
    )
    (net (code "113") (name "/TIMER5") (class "Default")
      (node (ref "U5") (pin "T6") (pinfunction "GPMC_BE0N_CLE/TIMER5/GPIO2_5_T6") (pintype "bidirectional"))
    )
    (net (code "114") (name "/TIMER6") (class "Default")
      (node (ref "U5") (pin "U6") (pinfunction "GPMC_WEN/TIMER6/GPIO2_4_U6") (pintype "bidirectional"))
    )
    (net (code "115") (name "/TIMER7") (class "Default")
      (node (ref "U5") (pin "T7") (pinfunction "GPMC_OEN_REN/TIMER7/EMU4/GPIO2_3_T7") (pintype "bidirectional"))
    )
    (net (code "116") (name "/U5_R13") (class "Default")
      (node (ref "R160") (pin "1") (pinfunction "1_1") (pintype "passive"))
      (node (ref "U5") (pin "R13") (pinfunction "GPMC_A0/GMII2_TXEN/RGMII2_TCTL/RMII2_TXEN/GPMC_A16/PR1_MII_MT1_CLK/EHRPWM1_TRIPZONE_INPUT/GPIO1_16_R13") (pintype "output"))
    )
    (net (code "117") (name "/U5_T13") (class "Default")
      (node (ref "R161") (pin "1") (pinfunction "1_1") (pintype "passive"))
      (node (ref "U5") (pin "T13") (pinfunction "GPMC_CSN3/MMC2_CMD/PR1_MDIO_DATA/GPIO2_0_T13") (pintype "bidirectional"))
    )
    (net (code "118") (name "/UART4_RXD") (class "Default")
      (node (ref "U5") (pin "T17") (pinfunction "GPMC_WAIT0/GM112_CRS/GPMC_CSN4/RMII2_CRS_DV/MMC1_SDCD/PR1_MII1_RXDV/UART4_RXD/GPIO0_30_T17") (pintype "bidirectional"))
    )
    (net (code "119") (name "/UART4_TXD") (class "Default")
      (node (ref "U5") (pin "U17") (pinfunction "GPMC_WPN/GMII2_RXERR/GPMC_CSN5/RMII2_RXERR/MMC2_SDCD/PR1_MDIO_MDCLK/UART4_TXD/GPIO0_31_U17") (pintype "bidirectional"))
    )
    (net (code "120") (name "/USB1_OCn") (class "Default")
      (node (ref "U5") (pin "T16") (pinfunction "GPMC_A10/GMII2_RXD1/RGMII2_RD1/RMII2_RXD1/GPMC_A26/PR1_MII1_CRS/MCASP0_AXR0/GPIO1_26_T16") (pintype "output"))
    )
    (net (code "121") (name "/USR0") (class "Default")
      (node (ref "U5") (pin "V15") (pinfunction "GPMC_A5/GMII2_TXD0/RGMII2_TD0/RMII2_TXD0/GPMC_A21/PR1_MII1_RXD3/EQEP1B_IN/GPIO1_21_V15") (pintype "output"))
    )
    (net (code "122") (name "/USR1") (class "Default")
      (node (ref "U5") (pin "U15") (pinfunction "GPMC_A6/GMII2_TXCLK/RGMII2_TCLK/MMC2_DAT4/GPMC_A22/PR1_MII1_RXD2/EQEP1_INDEX/GPIO1_22_U15") (pintype "output"))
    )
    (net (code "123") (name "/USR2") (class "Default")
      (node (ref "U5") (pin "T15") (pinfunction "GPMC_A7/GMII2_RXCLK/RGMII2_RCLK/MMC2_DAT5/GPMC_A23/PR1_MII1_RXD1/EQEP1_STROBE/GPIO1_23_T15") (pintype "output"))
    )
    (net (code "124") (name "/USR3") (class "Default")
      (node (ref "U5") (pin "V16") (pinfunction "GPMC_A8/GMII2_RXD3/RGMII2_RD3/MMC2_DAT6/GPMC_A24/PR1_MII1_RXD0/MCASP0_ACLKX/GPIO1_24_V16") (pintype "output"))
    )
    (net (code "125") (name "/XDMA_EVENT_INTR0") (class "Default")
      (node (ref "P2") (pin "17") (pinfunction "EMU2_17") (pintype "passive"))
      (node (ref "R18") (pin "2") (pinfunction "2_2") (pintype "passive"))
      (node (ref "U6") (pin "1") (pinfunction "CLK_1") (pintype "input"))
    )
    (net (code "126") (name "/eMMC_RSTn") (class "Default")
      (node (ref "R162") (pin "2") (pinfunction "2_2") (pintype "passive"))
    )
    (net (code "127") (name "DDR_VREF") (class "Default")
      (node (ref "C28") (pin "1") (pinfunction "1_1") (pintype "passive"))
      (node (ref "U5") (pin "J4") (pinfunction "VREFSSTL_J4") (pintype "passive"))
    )
    (net (code "128") (name "DGND") (class "Default")
      (node (ref "C158") (pin "2") (pinfunction "2_2") (pintype "passive"))
      (node (ref "C159") (pin "2") (pinfunction "2_2") (pintype "passive"))
      (node (ref "C24") (pin "2") (pinfunction "2_2") (pintype "passive"))
      (node (ref "C27") (pin "2") (pinfunction "2_2") (pintype "passive"))
      (node (ref "C28") (pin "2") (pinfunction "2_2") (pintype "passive"))
      (node (ref "C29") (pin "2") (pinfunction "2_2") (pintype "passive"))
      (node (ref "C30") (pin "2") (pinfunction "2_2") (pintype "passive"))
      (node (ref "P2") (pin "10") (pinfunction "GND_10") (pintype "power_in"))
      (node (ref "P2") (pin "12") (pinfunction "GND_12") (pintype "power_in"))
      (node (ref "P2") (pin "16") (pinfunction "GND_16") (pintype "power_in"))
      (node (ref "P2") (pin "20") (pinfunction "GND_20") (pintype "power_in"))
      (node (ref "P2") (pin "4") (pinfunction "TDIS_4") (pintype "passive"))
      (node (ref "P2") (pin "8") (pinfunction "GND_8") (pintype "power_in"))
      (node (ref "R22") (pin "1") (pinfunction "1_1") (pintype "passive"))
      (node (ref "R25") (pin "2") (pinfunction "2_2") (pintype "passive"))
      (node (ref "S1") (pin "1") (pinfunction "A1_1") (pintype "passive"))
      (node (ref "S1") (pin "3") (pinfunction "A3_3") (pintype "passive"))
      (node (ref "U3") (pin "3") (pinfunction "GND_3") (pintype "power_in"))
      (node (ref "U6") (pin "4") (pinfunction "GND_4") (pintype "power_in"))
      (node (ref "Y4") (pin "2") (pinfunction "GND_2") (pintype "power_in"))
    )
    (net (code "129") (name "GND_OSC0") (class "Default")
      (node (ref "C25") (pin "2") (pinfunction "2_2") (pintype "passive"))
      (node (ref "C26") (pin "2") (pinfunction "2_2") (pintype "passive"))
      (node (ref "U5") (pin "V11") (pinfunction "VSS_OSC0_V11") (pintype "power_in"))
    )
    (net (code "130") (name "Net-(U3-A)") (class "Default")
      (node (ref "U3") (pin "2") (pinfunction "A_2") (pintype "input"))
      (node (ref "U5") (pin "R14") (pinfunction "GPMC_A4/GMII2_TXD1/RGMII2_TD1/RMII2_TXD1/GPMC_A20/PR1_MII1_TXD0/EQEP1A_IN/GPIO1_20_R14") (pintype "output"))
    )
    (net (code "131") (name "Net-(U3-Y)") (class "Default")
      (node (ref "R162") (pin "1") (pinfunction "1_1") (pintype "passive"))
      (node (ref "U3") (pin "4") (pinfunction "Y_4") (pintype "open_collector"))
    )
    (net (code "132") (name "Net-(U6-Q)") (class "Default")
      (node (ref "R21") (pin "1") (pinfunction "1_1") (pintype "passive"))
      (node (ref "U6") (pin "5") (pinfunction "Q_5") (pintype "output"))
    )
    (net (code "133") (name "Net-(Y4-CLK)") (class "Default")
      (node (ref "R167") (pin "1") (pinfunction "1_1") (pintype "passive"))
      (node (ref "Y4") (pin "3") (pinfunction "CLK_3") (pintype "output"))
    )
    (net (code "134") (name "VDD_3V3A") (class "Default")
      (node (ref "C158") (pin "1") (pinfunction "1_1") (pintype "passive"))
      (node (ref "C159") (pin "1") (pinfunction "1_1") (pintype "passive"))
      (node (ref "C27") (pin "1") (pinfunction "1_1") (pintype "passive"))
      (node (ref "R14") (pin "1") (pinfunction "1_1") (pintype "passive"))
      (node (ref "U3") (pin "5") (pinfunction "VCC_5") (pintype "power_in"))
      (node (ref "U6") (pin "6") (pinfunction "~{CLR}_6") (pintype "input"))
      (node (ref "U6") (pin "7") (pinfunction "~{PRE}_7") (pintype "input"))
      (node (ref "U6") (pin "8") (pinfunction "VCC_8") (pintype "power_in"))
      (node (ref "Y4") (pin "4") (pinfunction "VCC_4") (pintype "power_in"))
    )
    (net (code "135") (name "VDD_3V3B") (class "Default")
      (node (ref "C29") (pin "1") (pinfunction "1_1") (pintype "passive"))
      (node (ref "P2") (pin "5") (pinfunction "TVDD_5") (pintype "passive"))
      (node (ref "R23") (pin "1") (pinfunction "1_1") (pintype "passive"))
      (node (ref "R24") (pin "1") (pinfunction "1_1") (pintype "passive"))
    )
    (net (code "136") (name "unconnected-(P2-NC-Pad6)") (class "Default")
      (node (ref "P2") (pin "6") (pinfunction "NC_6") (pintype "passive+no_connect"))
    )
    (net (code "137") (name "unconnected-(U3-NC-Pad1)") (class "Default")
      (node (ref "U3") (pin "1") (pinfunction "NC_1") (pintype "passive+no_connect"))
    )
    (net (code "138") (name "unconnected-(Y1-Pad2)") (class "Default")
      (node (ref "Y1") (pin "2") (pinfunction "2_2") (pintype "passive"))
    )
    (net (code "139") (name "unconnected-(Y1-Pad3)") (class "Default")
      (node (ref "Y1") (pin "3") (pinfunction "3_3") (pintype "passive"))
    )
  )
)
